# SignalAnalyse.net
KiCad netlist of a schematic drawn in Altium Designer
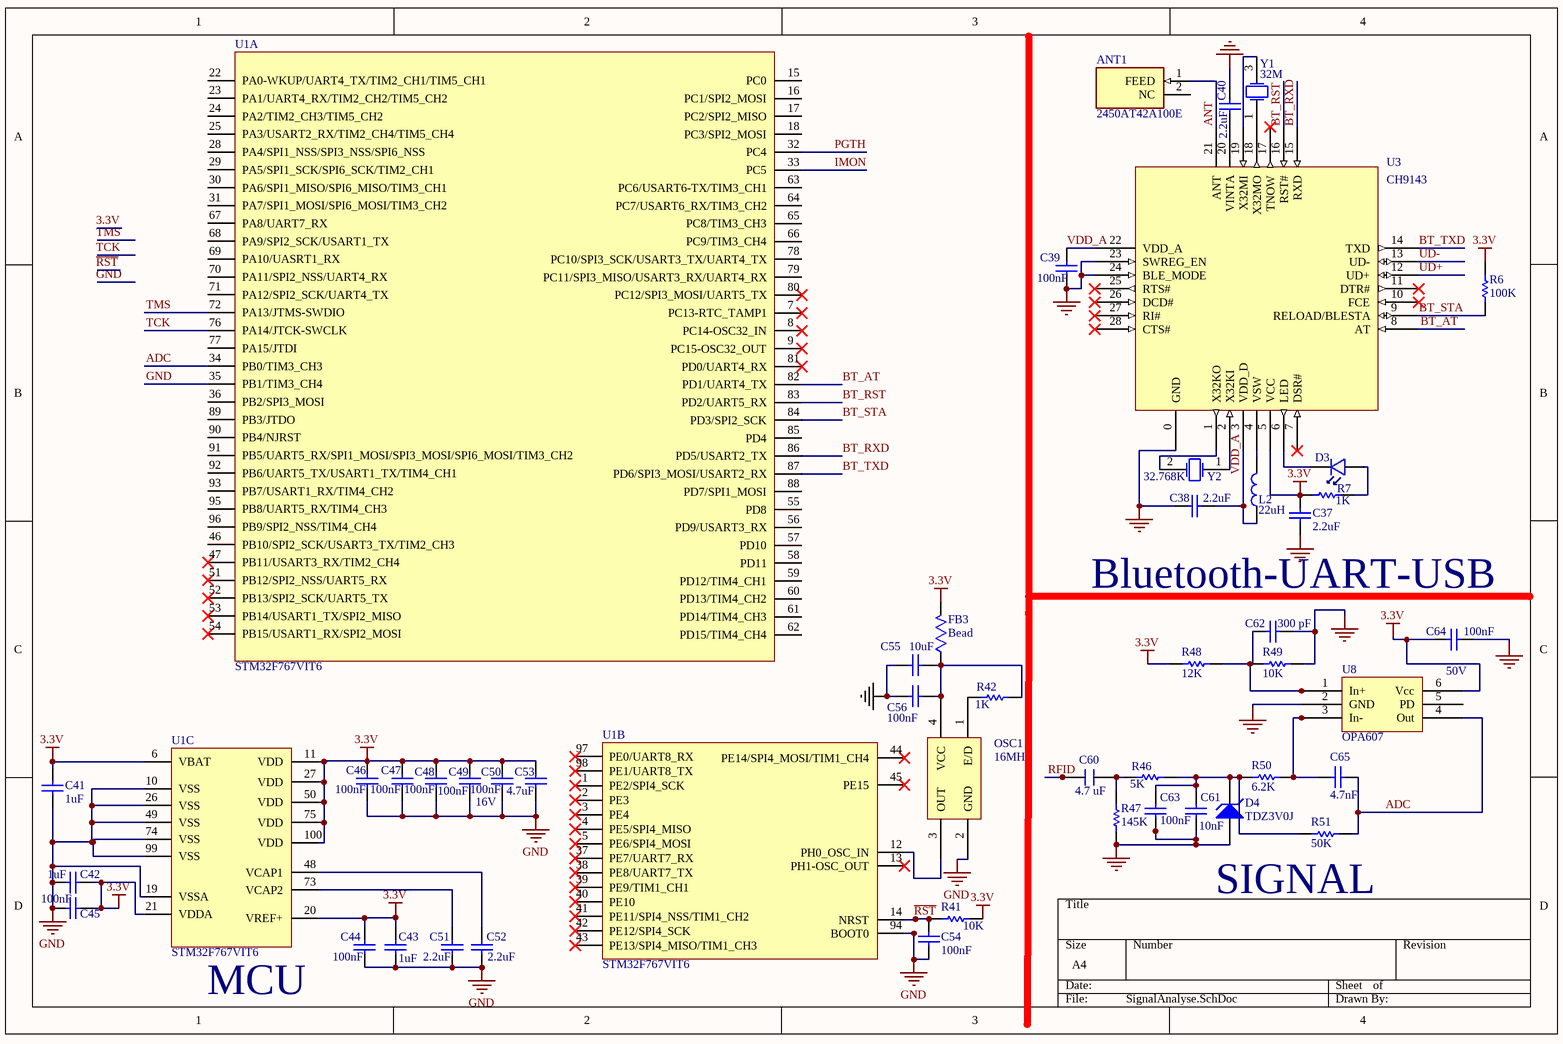
[diagram p0: SignalAnalyse.SchDoc]

(export (version "E")
  (design (tool "Eeschema 10.0.6"))
  (components
    (comp (ref "ANT1")
      (value "2450AT42A100E")
      (footprint "SamacSys:ANTC5020X110N")
      (description "Antenna")
      (fields (field (name "MOUSER PART NUMBER") "609-2450AT42A100E"))
      (libsource (lib "*") (part "2450AT42A100E"))
    )
    (comp (ref "C37")
      (value "2.2uF")
      (footprint "0603")
      (description "Capacitor (Semiconductor SIM Model)")
      (fields
        (field (name "VOLTAGE") "10V")
        (field (name "Comment") "GRM188R61A226ME15D")
        (field (name "PUBLISHER") "Altium Limited")
      )
      (libsource (lib "Miscellaneous Devices") (part "Cap Semi"))
    )
    (comp (ref "C38")
      (value "2.2uF")
      (footprint "0603")
      (description "Capacitor (Semiconductor SIM Model)")
      (fields
        (field (name "VOLTAGE") "10V")
        (field (name "Comment") "GRM188R61A226ME15D")
        (field (name "PUBLISHER") "Altium Limited")
      )
      (libsource (lib "Miscellaneous Devices") (part "Cap Semi"))
    )
    (comp (ref "C39")
      (value "100nF")
      (footprint "1608[0603]")
      (description "多层陶瓷电容器MLCC - SMD/SMT 0.1UF 16V 10% 0603")
      (fields
        (field (name "VOLTAGE") "16V")
        (field (name "PART NUMBER") "GCM188R71C104KA37J")
        (field (name "PUBLISHER") "Altium Limited")
      )
      (libsource (lib "Miscellaneous Devices") (part "Cap Semi"))
    )
    (comp (ref "C40")
      (value "2.2uF")
      (footprint "1608[0603]")
      (description "Capacitor (Semiconductor SIM Model)")
      (fields
        (field (name "VOLTAGE") "10V")
        (field (name "Comment") "GRM188R61A226ME15D")
        (field (name "PUBLISHER") "Altium Limited")
      )
      (libsource (lib "Miscellaneous Devices") (part "Cap Semi"))
    )
    (comp (ref "C41")
      (value "1uF")
      (footprint "1608[0603]")
      (description "Capacitor (Semiconductor SIM Model)")
      (fields
        (field (name "VOLTAGE") "50V")
        (field (name "Comment") "GRM188R61A226ME15D")
        (field (name "PUBLISHER") "Altium Limited")
      )
      (libsource (lib "Miscellaneous Devices") (part "Cap Semi"))
    )
    (comp (ref "C42")
      (value "1uF")
      (footprint "1608[0603]")
      (description "Capacitor (Semiconductor SIM Model)")
      (fields
        (field (name "VOLTAGE") "50V")
        (field (name "Comment") "GRM188R61A226ME15D")
        (field (name "PUBLISHER") "Altium Limited")
      )
      (libsource (lib "Miscellaneous Devices") (part "Cap Semi"))
    )
    (comp (ref "C43")
      (value "1uF")
      (footprint "1608[0603]")
      (description "Capacitor (Semiconductor SIM Model)")
      (fields
        (field (name "VOLTAGE") "50V")
        (field (name "Comment") "GRM188R61A226ME15D")
        (field (name "PUBLISHER") "Altium Limited")
      )
      (libsource (lib "Miscellaneous Devices") (part "Cap Semi"))
    )
    (comp (ref "C44")
      (value "100nF")
      (footprint "1608[0603]")
      (description "多层陶瓷电容器MLCC - SMD/SMT 0.1UF 16V 10% 0603")
      (fields
        (field (name "VOLTAGE") "16V")
        (field (name "PART NUMBER") "GCM188R71C104KA37J")
        (field (name "PUBLISHER") "Altium Limited")
      )
      (libsource (lib "Miscellaneous Devices") (part "Cap Semi"))
    )
    (comp (ref "C45")
      (value "100nF")
      (footprint "1608[0603]")
      (description "多层陶瓷电容器MLCC - SMD/SMT 0.1UF 16V 10% 0603")
      (fields
        (field (name "VOLTAGE") "16V")
        (field (name "PART NUMBER") "GCM188R71C104KA37J")
        (field (name "PUBLISHER") "Altium Limited")
      )
      (libsource (lib "Miscellaneous Devices") (part "Cap Semi"))
    )
    (comp (ref "C46")
      (value "100nF")
      (footprint "1608[0603]")
      (description "多层陶瓷电容器MLCC - SMD/SMT 0.1UF 16V 10% 0603")
      (fields
        (field (name "VOLTAGE") "16V")
        (field (name "PART NUMBER") "GCM188R71C104KA37J")
        (field (name "PUBLISHER") "Altium Limited")
      )
      (libsource (lib "Miscellaneous Devices") (part "Cap Semi"))
    )
    (comp (ref "C47")
      (value "100nF")
      (footprint "1608[0603]")
      (description "多层陶瓷电容器MLCC - SMD/SMT 0.1UF 16V 10% 0603")
      (fields
        (field (name "VOLTAGE") "16V")
        (field (name "PART NUMBER") "GCM188R71C104KA37J")
        (field (name "PUBLISHER") "Altium Limited")
      )
      (libsource (lib "Miscellaneous Devices") (part "Cap Semi"))
    )
    (comp (ref "C48")
      (value "100nF")
      (footprint "1608[0603]")
      (description "多层陶瓷电容器MLCC - SMD/SMT 0.1UF 16V 10% 0603")
      (fields
        (field (name "VOLTAGE") "16V")
        (field (name "PART NUMBER") "GCM188R71C104KA37J")
        (field (name "PUBLISHER") "Altium Limited")
      )
      (libsource (lib "Miscellaneous Devices") (part "Cap Semi"))
    )
    (comp (ref "C49")
      (value "100nF")
      (footprint "1608[0603]")
      (description "多层陶瓷电容器MLCC - SMD/SMT 0.1UF 16V 10% 0603")
      (fields
        (field (name "VOLTAGE") "16V")
        (field (name "PART NUMBER") "GCM188R71C104KA37J")
        (field (name "PUBLISHER") "Altium Limited")
      )
      (libsource (lib "Miscellaneous Devices") (part "Cap Semi"))
    )
    (comp (ref "C50")
      (value "100nF")
      (footprint "1608[0603]")
      (description "多层陶瓷电容器MLCC - SMD/SMT 0.1UF 16V 10% 0603")
      (fields
        (field (name "VOLTAGE") "16V")
        (field (name "PART NUMBER") "GCM188R71C104KA37J")
        (field (name "Comment") "Cap 100nF")
        (field (name "PUBLISHER") "Altium Limited")
      )
      (libsource (lib "Miscellaneous Devices") (part "Cap Semi"))
    )
    (comp (ref "C51")
      (value "2.2uF")
      (footprint "1608[0603]")
      (description "Capacitor (Semiconductor SIM Model)")
      (fields
        (field (name "VOLTAGE") "16V")
        (field (name "Comment") "GRM188R61A226ME15D")
        (field (name "PUBLISHER") "Altium Limited")
      )
      (libsource (lib "Miscellaneous Devices") (part "Cap Semi"))
    )
    (comp (ref "C52")
      (value "2.2uF")
      (footprint "1608[0603]")
      (description "Capacitor (Semiconductor SIM Model)")
      (fields
        (field (name "VOLTAGE") "16V")
        (field (name "Comment") "GRM188R61A226ME15D")
        (field (name "PUBLISHER") "Altium Limited")
      )
      (libsource (lib "Miscellaneous Devices") (part "Cap Semi"))
    )
    (comp (ref "C53")
      (value "4.7uF")
      (footprint "1608[0603]")
      (description "Capacitor (Semiconductor SIM Model)")
      (fields
        (field (name "VOLTAGE") "10V")
        (field (name "Comment") "GRM188R61A226ME15D")
        (field (name "PUBLISHER") "Altium Limited")
      )
      (libsource (lib "Miscellaneous Devices") (part "Cap Semi"))
    )
    (comp (ref "C54")
      (value "100nF")
      (footprint "1608[0603]")
      (description "多层陶瓷电容器MLCC - SMD/SMT 0.1UF 16V 10% 0603")
      (fields
        (field (name "VOLTAGE") "16V")
        (field (name "PART NUMBER") "GCM188R71C104KA37J")
        (field (name "PUBLISHER") "Altium Limited")
      )
      (libsource (lib "Miscellaneous Devices") (part "Cap Semi"))
    )
    (comp (ref "C55")
      (value "10uF")
      (footprint "1608[0603]")
      (description "多层陶瓷电容器MLCC - SMD/SMT 10UF 25V 10% 0603")
      (fields
        (field (name "VOLTAGE") "25V")
        (field (name "PART NUMBER") "GRM188R61E106KA73D")
        (field (name "PUBLISHER") "Altium Limited")
      )
      (libsource (lib "Miscellaneous Devices") (part "Cap Semi"))
    )
    (comp (ref "C56")
      (value "100nF")
      (footprint "1608[0603]")
      (description "多层陶瓷电容器MLCC - SMD/SMT 0.1UF 16V 10% 0603")
      (fields
        (field (name "VOLTAGE") "16V")
        (field (name "PART NUMBER") "GCM188R71C104KA37J")
        (field (name "PUBLISHER") "Altium Limited")
      )
      (libsource (lib "Miscellaneous Devices") (part "Cap Semi"))
    )
    (comp (ref "C60")
      (value "4.7 uF")
      (footprint "0603")
      (description "多层陶瓷电容器MLCC - SMD/SMT 0603 4.7uF 25V X5R 20%")
      (fields (field (name "VOLTAGE") "25V") (field (name "PART NUMBER") "GRM188R61E475ME11J"))
      (libsource (lib "Integrated_Library") (part "C-Ceramic"))
    )
    (comp (ref "C61")
      (value "10nF")
      (footprint "1608[0603]")
      (description "多层陶瓷电容器MLCC - SMD/SMT 0.01UF 25V 5% 0603 C0G")
      (fields
        (field (name "VOLTAGE") "25V")
        (field (name "PART NUMBER") "GRM1885C1E103JA01D")
        (field (name "PUBLISHER") "Altium Limited")
      )
      (libsource (lib "Miscellaneous Devices") (part "Cap Semi"))
    )
    (comp (ref "C62")
      (value "300 pF")
      (footprint "1608[0603]")
      (description "多层陶瓷电容器MLCC - SMD/SMT 0603 300pF 50volts C0G 2%")
      (fields
        (field (name "VOLTAGE") "50V")
        (field (name "PART NUMBER") "GRM1885C1H301GA01D")
        (field (name "PUBLISHER") "Altium Limited")
      )
      (libsource (lib "Miscellaneous Devices") (part "Cap Semi"))
    )
    (comp (ref "C63")
      (value "100nF")
      (footprint "1608[0603]")
      (description "多层陶瓷电容器MLCC - SMD/SMT 100nF+/-10% 50V X7R 1608")
      (fields
        (field (name "VOLTAGE") "50V")
        (field (name "PART NUMBER") "CL10B104KB8NNNC")
        (field (name "PUBLISHER") "Altium Limited")
      )
      (libsource (lib "Miscellaneous Devices") (part "Cap Semi"))
    )
    (comp (ref "C64")
      (value "100nF")
      (footprint "1608[0603]")
      (description "多层陶瓷电容器MLCC - SMD/SMT 100nF+/-10% 50V X7R 1608")
      (fields
        (field (name "VOLTAGE") "50V")
        (field (name "PART NUMBER") "GCM188R71C104KA37J")
        (field (name "Comment") "Cap 100nF")
        (field (name "PUBLISHER") "Altium Limited")
      )
      (libsource (lib "Miscellaneous Devices") (part "Cap Semi"))
    )
    (comp (ref "C65")
      (value "4.7nF")
      (footprint "1608[0603]")
      (description "多层陶瓷电容器MLCC - SMD/SMT 16V 4700pF X7R 0603 10%")
      (fields
        (field (name "VOLTAGE") "16V")
        (field (name "PART NUMBER") "CC0603KRX7R7BB472")
        (field (name "PUBLISHER") "Altium Limited")
      )
      (libsource (lib "Miscellaneous Devices") (part "Cap Semi"))
    )
    (comp (ref "D3")
      (value "LED-Green")
      (footprint "D0805")
      (libsource (lib "Integrated_Library") (part "LED"))
    )
    (comp (ref "D4")
      (value "TDZ3V0J")
      (footprint "SOD-323")
      (description "Zener Diode 3V")
      (fields (field (name "PUBLISHER") "Altium Limited"))
      (libsource (lib "Miscellaneous Devices") (part "D Zener"))
    )
    (comp (ref "FB3")
      (value "Bead")
      (footprint "SamacSys:BEADC2012X110N")
      (description "Wurth Ferrite Bead")
      (fields (field (name "MANUFACTURER_PART_NUMBER") "782853200"))
      (libsource (lib "SamacSys") (part "782853200"))
    )
    (comp (ref "L2")
      (value "22uH")
      (footprint "L0805")
      (fields (field (name "PART NUMBER") "MGFL2012F220") (field (name "MANUFACTURER") "microgate"))
      (libsource (lib "Integrated_Library") (part "FB"))
    )
    (comp (ref "OSC1")
      (value "16MHz")
      (footprint "OSC_3.2X2.5")
      (description "OSC with disable function")
      (libsource (lib "Integrated_Library") (part "OSC2"))
    )
    (comp (ref "R6")
      (value "100K")
      (footprint "J1-0603")
      (description "Resistor")
      (fields
        (field (name "PART NUMBER") "RC0603FR-07100KL")
        (field (name "MANUFACTURER") "YAGEO")
        (field (name "PUBLISHER") "Altium Limited")
      )
      (libsource (lib "Miscellaneous Devices") (part "Res1"))
    )
    (comp (ref "R7")
      (value "1K")
      (footprint "J1-0603")
      (description "Resistor")
      (fields
        (field (name "PART NUMBER") "RC0603FR-071KL")
        (field (name "MANUFACTURER") "YAGEO")
        (field (name "PUBLISHER") "Altium Limited")
      )
      (libsource (lib "Miscellaneous Devices") (part "Res1"))
    )
    (comp (ref "R41")
      (value "10K")
      (footprint "J1-0603")
      (description "Resistor")
      (fields
        (field (name "PART NUMBER") "RC0603FR-0710KL")
        (field (name "MANUFACTURER") "YAGEO")
        (field (name "PUBLISHER") "Altium Limited")
      )
      (libsource (lib "Miscellaneous Devices") (part "Res1"))
    )
    (comp (ref "R42")
      (value "1K")
      (footprint "J1-0603")
      (description "Resistor")
      (fields
        (field (name "PART NUMBER") "RC0603FR-071KL")
        (field (name "MANUFACTURER") "YAGEO")
        (field (name "PUBLISHER") "Altium Limited")
      )
      (libsource (lib "Miscellaneous Devices") (part "Res1"))
    )
    (comp (ref "R46")
      (value "5K")
      (footprint "J1-0603")
      (description "Resistor")
      (fields
        (field (name "PART NUMBER") "RC0603FR-071KL")
        (field (name "MANUFACTURER") "YAGEO")
        (field (name "PUBLISHER") "Altium Limited")
      )
      (libsource (lib "Miscellaneous Devices") (part "Res1"))
    )
    (comp (ref "R47")
      (value "145K")
      (footprint "J1-0603")
      (description "Resistor")
      (fields
        (field (name "PART NUMBER") "RC0603FR-0710KL")
        (field (name "MANUFACTURER") "YAGEO")
        (field (name "PUBLISHER") "Altium Limited")
      )
      (libsource (lib "Miscellaneous Devices") (part "Res1"))
    )
    (comp (ref "R48")
      (value "12K")
      (footprint "J1-0603")
      (description "Resistor")
      (fields
        (field (name "PART NUMBER") "RC0603FR-0710KL")
        (field (name "MANUFACTURER") "YAGEO")
        (field (name "PUBLISHER") "Altium Limited")
      )
      (libsource (lib "Miscellaneous Devices") (part "Res1"))
    )
    (comp (ref "R49")
      (value "10K")
      (footprint "J1-0603")
      (description "Resistor")
      (fields
        (field (name "PART NUMBER") "RC0603FR-0710KL")
        (field (name "MANUFACTURER") "YAGEO")
        (field (name "PUBLISHER") "Altium Limited")
      )
      (libsource (lib "Miscellaneous Devices") (part "Res1"))
    )
    (comp (ref "R50")
      (value "6.2K")
      (footprint "J1-0603")
      (description "Resistor")
      (fields
        (field (name "PART NUMBER") "RC0603FR-0710KL")
        (field (name "MANUFACTURER") "YAGEO")
        (field (name "PUBLISHER") "Altium Limited")
      )
      (libsource (lib "Miscellaneous Devices") (part "Res1"))
    )
    (comp (ref "R51")
      (value "50K")
      (footprint "J1-0603")
      (description "Resistor")
      (fields
        (field (name "PART NUMBER") "RC0603FR-0710KL")
        (field (name "MANUFACTURER") "YAGEO")
        (field (name "PUBLISHER") "Altium Limited")
      )
      (libsource (lib "Miscellaneous Devices") (part "Res1"))
    )
    (comp (ref "U1")
      (value "STM32F767VIT6")
      (footprint "STM32F767VIT6")
      (libsource (lib "") (part "STM32F767VIT6_1"))
    )
    (comp (ref "U3")
      (value "CH9143")
      (footprint "QFN28_4X4")
      (description "Bluetooth-LowEnergy & UART & USB Mutual Transport")
      (libsource (lib "CHXXX") (part "CH9143"))
    )
    (comp (ref "U8")
      (value "OPA607")
      (footprint "OPA607IDCKR")
      (libsource (lib "OPA607IDCKR") (part "TSV620AILT"))
    )
    (comp (ref "Y1")
      (value "32M")
      (footprint "SamacSys:SMD2016-4N")
      (description "Quartz Crystal Oscillator")
      (fields (field (name "MANUFACTURER_PART_NUMBER") "X201632MMB4SI"))
      (libsource (lib "SamacSys") (part "X201632MMB4SI"))
    )
    (comp (ref "Y2")
      (value "32.768K")
      (footprint "SamacSys:Q13FC1350000400")
      (description "Crystal Oscillator")
      (fields (field (name "MANUFACTURER_PART_NUMBER") "Q13FC1350000400"))
      (libsource (lib "SamacSys") (part "Q13FC1350000400"))
    )
  )
  (nets
    (net (code "1") (name "/ADC") (class "Default")
      (node (ref "C65") (pin "1") (pinfunction "1_1") (pintype "passive"))
      (node (ref "R51") (pin "1") (pinfunction "1_1") (pintype "passive"))
      (node (ref "U1") (pin "34") (pinfunction "PB0/TIM3_CH3_34") (pintype "passive"))
      (node (ref "U8") (pin "4") (pinfunction "Out_4") (pintype "passive"))
    )
    (net (code "2") (name "/ANT") (class "Default")
      (node (ref "ANT1") (pin "1") (pinfunction "FEED_1") (pintype "input"))
      (node (ref "U3") (pin "21") (pinfunction "ANT_21") (pintype "passive"))
    )
    (net (code "3") (name "/BT_AT") (class "Default")
      (node (ref "U1") (pin "82") (pinfunction "PD1/UART4_TX_82") (pintype "passive"))
      (node (ref "U3") (pin "8") (pinfunction "AT_8") (pintype "input"))
    )
    (net (code "4") (name "/BT_RST") (class "Default")
      (node (ref "U1") (pin "83") (pinfunction "PD2/UART5_RX_83") (pintype "passive"))
      (node (ref "U3") (pin "16") (pinfunction "RST#_16") (pintype "input"))
    )
    (net (code "5") (name "/BT_RXD") (class "Default")
      (node (ref "U1") (pin "86") (pinfunction "PD5/USART2_TX_86") (pintype "passive"))
      (node (ref "U3") (pin "15") (pinfunction "RXD_15") (pintype "input"))
    )
    (net (code "6") (name "/BT_STA") (class "Default")
      (node (ref "R6") (pin "2") (pinfunction "2_2") (pintype "passive"))
      (node (ref "U1") (pin "84") (pinfunction "PD3/SPI2_SCK_84") (pintype "passive"))
      (node (ref "U3") (pin "9") (pinfunction "RELOAD/BLESTA_9") (pintype "bidirectional"))
    )
    (net (code "7") (name "/BT_TXD") (class "Default")
      (node (ref "U1") (pin "87") (pinfunction "PD6/SPI3_MOSI/USART2_RX_87") (pintype "passive"))
      (node (ref "U3") (pin "14") (pinfunction "TXD_14") (pintype "output"))
    )
    (net (code "8") (name "/IMON") (class "Default")
      (node (ref "U1") (pin "33") (pinfunction "PC5_33") (pintype "passive"))
    )
    (net (code "9") (name "/PGTH") (class "Default")
      (node (ref "U1") (pin "32") (pinfunction "PC4_32") (pintype "passive"))
    )
    (net (code "10") (name "/RFID") (class "Default")
      (node (ref "C60") (pin "1") (pinfunction "1_1") (pintype "passive"))
    )
    (net (code "11") (name "/TCK") (class "Default")
      (node (ref "U1") (pin "76") (pinfunction "PA14/JTCK-SWCLK_76") (pintype "passive"))
    )
    (net (code "12") (name "/TMS") (class "Default")
      (node (ref "U1") (pin "72") (pinfunction "PA13/JTMS-SWDIO_72") (pintype "passive"))
    )
    (net (code "13") (name "/UD+") (class "Default")
      (node (ref "U3") (pin "12") (pinfunction "UD+_12") (pintype "bidirectional"))
    )
    (net (code "14") (name "/UD-") (class "Default")
      (node (ref "U3") (pin "13") (pinfunction "UD-_13") (pintype "bidirectional"))
    )
    (net (code "15") (name "/VDD_A") (class "Default")
      (node (ref "C38") (pin "2") (pinfunction "2_2") (pintype "passive"))
      (node (ref "C39") (pin "1") (pinfunction "1_1") (pintype "passive"))
      (node (ref "L2") (pin "1") (pinfunction "1_1") (pintype "passive"))
      (node (ref "U3") (pin "22") (pinfunction "VDD_A_22") (pintype "power_in"))
      (node (ref "U3") (pin "3") (pinfunction "VDD_D_3") (pintype "power_in"))
    )
    (net (code "16") (name "/~{RST}") (class "Default")
      (node (ref "C54") (pin "1") (pinfunction "1_1") (pintype "passive"))
      (node (ref "R41") (pin "1") (pinfunction "1_1") (pintype "passive"))
      (node (ref "U1") (pin "14") (pinfunction "NRST_14") (pintype "passive"))
    )
    (net (code "17") (name "3.3V") (class "Default")
      (node (ref "C37") (pin "2") (pinfunction "2_2") (pintype "passive"))
      (node (ref "C41") (pin "1") (pinfunction "1_1") (pintype "passive"))
      (node (ref "C42") (pin "1") (pinfunction "1_1") (pintype "passive"))
      (node (ref "C43") (pin "2") (pinfunction "2_2") (pintype "passive"))
      (node (ref "C44") (pin "2") (pinfunction "2_2") (pintype "passive"))
      (node (ref "C45") (pin "1") (pinfunction "1_1") (pintype "passive"))
      (node (ref "C46") (pin "2") (pinfunction "2_2") (pintype "passive"))
      (node (ref "C47") (pin "2") (pinfunction "2_2") (pintype "passive"))
      (node (ref "C48") (pin "2") (pinfunction "2_2") (pintype "passive"))
      (node (ref "C49") (pin "2") (pinfunction "2_2") (pintype "passive"))
      (node (ref "C50") (pin "2") (pinfunction "2_2") (pintype "passive"))
      (node (ref "C53") (pin "2") (pinfunction "2_2") (pintype "passive"))
      (node (ref "C64") (pin "2") (pinfunction "2_2") (pintype "passive"))
      (node (ref "FB3") (pin "2") (pinfunction "2_2") (pintype "passive"))
      (node (ref "R41") (pin "2") (pinfunction "2_2") (pintype "passive"))
      (node (ref "R48") (pin "2") (pinfunction "2_2") (pintype "passive"))
      (node (ref "R6") (pin "1") (pinfunction "1_1") (pintype "passive"))
      (node (ref "R7") (pin "1") (pinfunction "1_1") (pintype "passive"))
      (node (ref "U1") (pin "100") (pinfunction "VDD_100") (pintype "passive"))
      (node (ref "U1") (pin "11") (pinfunction "VDD_11") (pintype "passive"))
      (node (ref "U1") (pin "20") (pinfunction "VREF+_20") (pintype "passive"))
      (node (ref "U1") (pin "21") (pinfunction "VDDA_21") (pintype "passive"))
      (node (ref "U1") (pin "27") (pinfunction "VDD_27") (pintype "passive"))
      (node (ref "U1") (pin "50") (pinfunction "VDD_50") (pintype "passive"))
      (node (ref "U1") (pin "6") (pinfunction "VBAT_6") (pintype "passive"))
      (node (ref "U1") (pin "75") (pinfunction "VDD_75") (pintype "passive"))
      (node (ref "U3") (pin "5") (pinfunction "VCC_5") (pintype "power_in"))
      (node (ref "U8") (pin "6") (pinfunction "Vcc_6") (pintype "passive"))
    )
    (net (code "18") (name "GND") (class "Default")
      (node (ref "C37") (pin "1") (pinfunction "1_1") (pintype "passive"))
      (node (ref "C38") (pin "1") (pinfunction "1_1") (pintype "passive"))
      (node (ref "C39") (pin "2") (pinfunction "2_2") (pintype "passive"))
      (node (ref "C40") (pin "1") (pinfunction "1_1") (pintype "passive"))
      (node (ref "C41") (pin "2") (pinfunction "2_2") (pintype "passive"))
      (node (ref "C42") (pin "2") (pinfunction "2_2") (pintype "passive"))
      (node (ref "C43") (pin "1") (pinfunction "1_1") (pintype "passive"))
      (node (ref "C44") (pin "1") (pinfunction "1_1") (pintype "passive"))
      (node (ref "C45") (pin "2") (pinfunction "2_2") (pintype "passive"))
      (node (ref "C46") (pin "1") (pinfunction "1_1") (pintype "passive"))
      (node (ref "C47") (pin "1") (pinfunction "1_1") (pintype "passive"))
      (node (ref "C48") (pin "1") (pinfunction "1_1") (pintype "passive"))
      (node (ref "C49") (pin "1") (pinfunction "1_1") (pintype "passive"))
      (node (ref "C50") (pin "1") (pinfunction "1_1") (pintype "passive"))
      (node (ref "C51") (pin "1") (pinfunction "1_1") (pintype "passive"))
      (node (ref "C52") (pin "1") (pinfunction "1_1") (pintype "passive"))
      (node (ref "C53") (pin "1") (pinfunction "1_1") (pintype "passive"))
      (node (ref "C54") (pin "2") (pinfunction "2_2") (pintype "passive"))
      (node (ref "C55") (pin "2") (pinfunction "2_2") (pintype "passive"))
      (node (ref "C56") (pin "2") (pinfunction "2_2") (pintype "passive"))
      (node (ref "C61") (pin "1") (pinfunction "1_1") (pintype "passive"))
      (node (ref "C62") (pin "1") (pinfunction "1_1") (pintype "passive"))
      (node (ref "C63") (pin "1") (pinfunction "1_1") (pintype "passive"))
      (node (ref "C64") (pin "1") (pinfunction "1_1") (pintype "passive"))
      (node (ref "D4") (pin "1") (pinfunction "A_1") (pintype "passive"))
      (node (ref "OSC1") (pin "2") (pinfunction "GND_2") (pintype "passive"))
      (node (ref "R47") (pin "2") (pinfunction "2_2") (pintype "passive"))
      (node (ref "R49") (pin "2") (pinfunction "2_2") (pintype "passive"))
      (node (ref "U1") (pin "10") (pinfunction "VSS_10") (pintype "passive"))
      (node (ref "U1") (pin "19") (pinfunction "VSSA_19") (pintype "passive"))
      (node (ref "U1") (pin "26") (pinfunction "VSS_26") (pintype "passive"))
      (node (ref "U1") (pin "35") (pinfunction "PB1/TIM3_CH4_35") (pintype "passive"))
      (node (ref "U1") (pin "49") (pinfunction "VSS_49") (pintype "passive"))
      (node (ref "U1") (pin "74") (pinfunction "VSS_74") (pintype "passive"))
      (node (ref "U1") (pin "94") (pinfunction "BOOT0_94") (pintype "passive"))
      (node (ref "U1") (pin "99") (pinfunction "VSS_99") (pintype "passive"))
      (node (ref "U3") (pin "0") (pinfunction "GND_0") (pintype "power_in"))
      (node (ref "U3") (pin "23") (pinfunction "SWREG_EN_23") (pintype "input"))
      (node (ref "U3") (pin "24") (pinfunction "BLE_MODE_24") (pintype "input"))
      (node (ref "U8") (pin "2") (pinfunction "GND_2") (pintype "passive"))
    )
    (net (code "19") (name "Net-(C60-Pad2)") (class "Default")
      (node (ref "C60") (pin "2") (pinfunction "2_2") (pintype "passive"))
      (node (ref "R46") (pin "1") (pinfunction "1_1") (pintype "passive"))
      (node (ref "R47") (pin "1") (pinfunction "1_1") (pintype "passive"))
    )
    (net (code "20") (name "Net-(D3-Pad1)") (class "Default")
      (node (ref "D3") (pin "1") (pinfunction "1_1") (pintype "passive"))
      (node (ref "R7") (pin "2") (pinfunction "2_2") (pintype "passive"))
    )
    (net (code "21") (name "Net-(D4-K)") (class "Default")
      (node (ref "C61") (pin "2") (pinfunction "2_2") (pintype "passive"))
      (node (ref "C63") (pin "2") (pinfunction "2_2") (pintype "passive"))
      (node (ref "D4") (pin "2") (pinfunction "K_2") (pintype "passive"))
      (node (ref "R46") (pin "2") (pinfunction "2_2") (pintype "passive"))
      (node (ref "R50") (pin "2") (pinfunction "2_2") (pintype "passive"))
      (node (ref "R51") (pin "2") (pinfunction "2_2") (pintype "passive"))
    )
    (net (code "22") (name "Net-(OSC1-E{slash}D)") (class "Default")
      (node (ref "OSC1") (pin "1") (pinfunction "E/D_1") (pintype "passive"))
      (node (ref "R42") (pin "1") (pinfunction "1_1") (pintype "passive"))
    )
    (net (code "23") (name "Net-(OSC1-OUT)") (class "Default")
      (node (ref "OSC1") (pin "3") (pinfunction "OUT_3") (pintype "passive"))
      (node (ref "U1") (pin "12") (pinfunction "PH0_OSC_IN_12") (pintype "passive"))
    )
    (net (code "24") (name "Net-(OSC1-VCC)") (class "Default")
      (node (ref "C55") (pin "1") (pinfunction "1_1") (pintype "passive"))
      (node (ref "C56") (pin "1") (pinfunction "1_1") (pintype "passive"))
      (node (ref "FB3") (pin "1") (pinfunction "1_1") (pintype "passive"))
      (node (ref "OSC1") (pin "4") (pinfunction "VCC_4") (pintype "passive"))
      (node (ref "R42") (pin "2") (pinfunction "2_2") (pintype "passive"))
    )
    (net (code "25") (name "Net-(U1C-VCAP1)") (class "Default")
      (node (ref "C52") (pin "2") (pinfunction "2_2") (pintype "passive"))
      (node (ref "U1") (pin "48") (pinfunction "VCAP1_48") (pintype "passive"))
    )
    (net (code "26") (name "Net-(U1C-VCAP2)") (class "Default")
      (node (ref "C51") (pin "2") (pinfunction "2_2") (pintype "passive"))
      (node (ref "U1") (pin "73") (pinfunction "VCAP2_73") (pintype "passive"))
    )
    (net (code "27") (name "Net-(U3-LED)") (class "Default")
      (node (ref "D3") (pin "2") (pinfunction "2_2") (pintype "passive"))
      (node (ref "U3") (pin "6") (pinfunction "LED_6") (pintype "output"))
    )
    (net (code "28") (name "Net-(U3-VINTA)") (class "Default")
      (node (ref "C40") (pin "2") (pinfunction "2_2") (pintype "passive"))
      (node (ref "U3") (pin "20") (pinfunction "VINTA_20") (pintype "power_in"))
    )
    (net (code "29") (name "Net-(U3-VSW)") (class "Default")
      (node (ref "L2") (pin "2") (pinfunction "2_2") (pintype "passive"))
      (node (ref "U3") (pin "4") (pinfunction "VSW_4") (pintype "power_in"))
    )
    (net (code "30") (name "Net-(U3-X32KI)") (class "Default")
      (node (ref "U3") (pin "2") (pinfunction "X32KI_2") (pintype "input"))
      (node (ref "Y2") (pin "1") (pinfunction "CRYSTAL_1_1") (pintype "passive"))
    )
    (net (code "31") (name "Net-(U3-X32KO)") (class "Default")
      (node (ref "U3") (pin "1") (pinfunction "X32KO_1") (pintype "output"))
      (node (ref "Y2") (pin "2") (pinfunction "CRYSTAL_2_2") (pintype "passive"))
    )
    (net (code "32") (name "Net-(U3-X32MI)") (class "Default")
      (node (ref "U3") (pin "19") (pinfunction "X32MI_19") (pintype "input"))
      (node (ref "Y1") (pin "3") (pinfunction "OSC2_3") (pintype "passive"))
    )
    (net (code "33") (name "Net-(U3-X32MO)") (class "Default")
      (node (ref "U3") (pin "18") (pinfunction "X32MO_18") (pintype "output"))
      (node (ref "Y1") (pin "1") (pinfunction "OSC1_1") (pintype "passive"))
    )
    (net (code "34") (name "Net-(U8-In+)") (class "Default")
      (node (ref "C62") (pin "2") (pinfunction "2_2") (pintype "passive"))
      (node (ref "R48") (pin "1") (pinfunction "1_1") (pintype "passive"))
      (node (ref "R49") (pin "1") (pinfunction "1_1") (pintype "passive"))
      (node (ref "U8") (pin "1") (pinfunction "In+_1") (pintype "passive"))
    )
    (net (code "35") (name "Net-(U8-In-)") (class "Default")
      (node (ref "C65") (pin "2") (pinfunction "2_2") (pintype "passive"))
      (node (ref "R50") (pin "1") (pinfunction "1_1") (pintype "passive"))
      (node (ref "U8") (pin "3") (pinfunction "In-_3") (pintype "passive"))
    )
    (net (code "36") (name "unconnected-(ANT1-NC-Pad2)") (class "Default")
      (node (ref "ANT1") (pin "2") (pinfunction "NC_2") (pintype "passive"))
    )
    (net (code "37") (name "unconnected-(U1A-PA0-WKUP{slash}UART4_TX{slash}TIM2_CH1{slash}TIM5_CH1-Pad22)") (class "Default")
      (node (ref "U1") (pin "22") (pinfunction "PA0-WKUP/UART4_TX/TIM2_CH1/TIM5_CH1_22") (pintype "passive"))
    )
    (net (code "38") (name "unconnected-(U1A-PA1{slash}UART4_RX{slash}TIM2_CH2{slash}TIM5_CH2-Pad23)") (class "Default")
      (node (ref "U1") (pin "23") (pinfunction "PA1/UART4_RX/TIM2_CH2/TIM5_CH2_23") (pintype "passive"))
    )
    (net (code "39") (name "unconnected-(U1A-PA2{slash}TIM2_CH3{slash}TIM5_CH2-Pad24)") (class "Default")
      (node (ref "U1") (pin "24") (pinfunction "PA2/TIM2_CH3/TIM5_CH2_24") (pintype "passive"))
    )
    (net (code "40") (name "unconnected-(U1A-PA3{slash}USART2_RX{slash}TIM2_CH4{slash}TIM5_CH4-Pad25)") (class "Default")
      (node (ref "U1") (pin "25") (pinfunction "PA3/USART2_RX/TIM2_CH4/TIM5_CH4_25") (pintype "passive"))
    )
    (net (code "41") (name "unconnected-(U1A-PA4{slash}SPI1_NSS{slash}SPI3_NSS{slash}SPI6_NSS-Pad28)") (class "Default")
      (node (ref "U1") (pin "28") (pinfunction "PA4/SPI1_NSS/SPI3_NSS/SPI6_NSS_28") (pintype "passive"))
    )
    (net (code "42") (name "unconnected-(U1A-PA5{slash}SPI1_SCK{slash}SPI6_SCK{slash}TIM2_CH1-Pad29)") (class "Default")
      (node (ref "U1") (pin "29") (pinfunction "PA5/SPI1_SCK/SPI6_SCK/TIM2_CH1_29") (pintype "passive"))
    )
    (net (code "43") (name "unconnected-(U1A-PA6{slash}SPI1_MISO{slash}SPI6_MISO{slash}TIM3_CH1-Pad30)") (class "Default")
      (node (ref "U1") (pin "30") (pinfunction "PA6/SPI1_MISO/SPI6_MISO/TIM3_CH1_30") (pintype "passive"))
    )
    (net (code "44") (name "unconnected-(U1A-PA7{slash}SPI1_MOSI{slash}SPI6_MOSI{slash}TIM3_CH2-Pad31)") (class "Default")
      (node (ref "U1") (pin "31") (pinfunction "PA7/SPI1_MOSI/SPI6_MOSI/TIM3_CH2_31") (pintype "passive"))
    )
    (net (code "45") (name "unconnected-(U1A-PA8{slash}UART7_RX-Pad67)") (class "Default")
      (node (ref "U1") (pin "67") (pinfunction "PA8/UART7_RX_67") (pintype "passive"))
    )
    (net (code "46") (name "unconnected-(U1A-PA9{slash}SPI2_SCK{slash}USART1_TX-Pad68)") (class "Default")
      (node (ref "U1") (pin "68") (pinfunction "PA9/SPI2_SCK/USART1_TX_68") (pintype "passive"))
    )
    (net (code "47") (name "unconnected-(U1A-PA10{slash}UASRT1_RX-Pad69)") (class "Default")
      (node (ref "U1") (pin "69") (pinfunction "PA10/UASRT1_RX_69") (pintype "passive"))
    )
    (net (code "48") (name "unconnected-(U1A-PA11{slash}SPI2_NSS{slash}UART4_RX-Pad70)") (class "Default")
      (node (ref "U1") (pin "70") (pinfunction "PA11/SPI2_NSS/UART4_RX_70") (pintype "passive"))
    )
    (net (code "49") (name "unconnected-(U1A-PA12{slash}SPI2_SCK{slash}UART4_TX-Pad71)") (class "Default")
      (node (ref "U1") (pin "71") (pinfunction "PA12/SPI2_SCK/UART4_TX_71") (pintype "passive"))
    )
    (net (code "50") (name "unconnected-(U1A-PA15{slash}JTDI-Pad77)") (class "Default")
      (node (ref "U1") (pin "77") (pinfunction "PA15/JTDI_77") (pintype "passive"))
    )
    (net (code "51") (name "unconnected-(U1A-PB2{slash}SPI3_MOSI-Pad36)") (class "Default")
      (node (ref "U1") (pin "36") (pinfunction "PB2/SPI3_MOSI_36") (pintype "passive"))
    )
    (net (code "52") (name "unconnected-(U1A-PB3{slash}JTDO-Pad89)") (class "Default")
      (node (ref "U1") (pin "89") (pinfunction "PB3/JTDO_89") (pintype "passive"))
    )
    (net (code "53") (name "unconnected-(U1A-PB4{slash}NJRST-Pad90)") (class "Default")
      (node (ref "U1") (pin "90") (pinfunction "PB4/NJRST_90") (pintype "passive"))
    )
    (net (code "54") (name "unconnected-(U1A-PB5{slash}UART5_RX{slash}SPI1_MOSI{slash}SPI3_MOSI{slash}SPI6_MOSI{slash}TIM3_CH2-Pad91)") (class "Default")
      (node (ref "U1") (pin "91") (pinfunction "PB5/UART5_RX/SPI1_MOSI/SPI3_MOSI/SPI6_MOSI/TIM3_CH2_91") (pintype "passive"))
    )
    (net (code "55") (name "unconnected-(U1A-PB6{slash}UART5_TX{slash}USART1_TX{slash}TIM4_CH1-Pad92)") (class "Default")
      (node (ref "U1") (pin "92") (pinfunction "PB6/UART5_TX/USART1_TX/TIM4_CH1_92") (pintype "passive"))
    )
    (net (code "56") (name "unconnected-(U1A-PB7{slash}USART1_RX{slash}TIM4_CH2-Pad93)") (class "Default")
      (node (ref "U1") (pin "93") (pinfunction "PB7/USART1_RX/TIM4_CH2_93") (pintype "passive"))
    )
    (net (code "57") (name "unconnected-(U1A-PB8{slash}UART5_RX{slash}TIM4_CH3-Pad95)") (class "Default")
      (node (ref "U1") (pin "95") (pinfunction "PB8/UART5_RX/TIM4_CH3_95") (pintype "passive"))
    )
    (net (code "58") (name "unconnected-(U1A-PB9{slash}SPI2_NSS{slash}TIM4_CH4-Pad96)") (class "Default")
      (node (ref "U1") (pin "96") (pinfunction "PB9/SPI2_NSS/TIM4_CH4_96") (pintype "passive"))
    )
    (net (code "59") (name "unconnected-(U1A-PB10{slash}SPI2_SCK{slash}USART3_TX{slash}TIM2_CH3-Pad46)") (class "Default")
      (node (ref "U1") (pin "46") (pinfunction "PB10/SPI2_SCK/USART3_TX/TIM2_CH3_46") (pintype "passive"))
    )
    (net (code "60") (name "unconnected-(U1A-PB11{slash}USART3_RX{slash}TIM2_CH4-Pad47)") (class "Default")
      (node (ref "U1") (pin "47") (pinfunction "PB11/USART3_RX/TIM2_CH4_47") (pintype "passive+no_connect"))
    )
    (net (code "61") (name "unconnected-(U1A-PB12{slash}SPI2_NSS{slash}UART5_RX-Pad51)") (class "Default")
      (node (ref "U1") (pin "51") (pinfunction "PB12/SPI2_NSS/UART5_RX_51") (pintype "passive+no_connect"))
    )
    (net (code "62") (name "unconnected-(U1A-PB13{slash}SPI2_SCK{slash}UART5_TX-Pad52)") (class "Default")
      (node (ref "U1") (pin "52") (pinfunction "PB13/SPI2_SCK/UART5_TX_52") (pintype "passive+no_connect"))
    )
    (net (code "63") (name "unconnected-(U1A-PB14{slash}USART1_TX{slash}SPI2_MISO-Pad53)") (class "Default")
      (node (ref "U1") (pin "53") (pinfunction "PB14/USART1_TX/SPI2_MISO_53") (pintype "passive+no_connect"))
    )
    (net (code "64") (name "unconnected-(U1A-PB15{slash}USART1_RX{slash}SPI2_MOSI-Pad54)") (class "Default")
      (node (ref "U1") (pin "54") (pinfunction "PB15/USART1_RX/SPI2_MOSI_54") (pintype "passive+no_connect"))
    )
    (net (code "65") (name "unconnected-(U1A-PC0-Pad15)") (class "Default")
      (node (ref "U1") (pin "15") (pinfunction "PC0_15") (pintype "passive"))
    )
    (net (code "66") (name "unconnected-(U1A-PC1{slash}SPI2_MOSI-Pad16)") (class "Default")
      (node (ref "U1") (pin "16") (pinfunction "PC1/SPI2_MOSI_16") (pintype "passive"))
    )
    (net (code "67") (name "unconnected-(U1A-PC2{slash}SPI2_MISO-Pad17)") (class "Default")
      (node (ref "U1") (pin "17") (pinfunction "PC2/SPI2_MISO_17") (pintype "passive"))
    )
    (net (code "68") (name "unconnected-(U1A-PC3{slash}SPI2_MOSI-Pad18)") (class "Default")
      (node (ref "U1") (pin "18") (pinfunction "PC3/SPI2_MOSI_18") (pintype "passive"))
    )
    (net (code "69") (name "unconnected-(U1A-PC6{slash}USART6-TX{slash}TIM3_CH1-Pad63)") (class "Default")
      (node (ref "U1") (pin "63") (pinfunction "PC6/USART6-TX/TIM3_CH1_63") (pintype "passive"))
    )
    (net (code "70") (name "unconnected-(U1A-PC7{slash}USART6_RX{slash}TIM3_CH2-Pad64)") (class "Default")
      (node (ref "U1") (pin "64") (pinfunction "PC7/USART6_RX/TIM3_CH2_64") (pintype "passive"))
    )
    (net (code "71") (name "unconnected-(U1A-PC8{slash}TIM3_CH3-Pad65)") (class "Default")
      (node (ref "U1") (pin "65") (pinfunction "PC8/TIM3_CH3_65") (pintype "passive"))
    )
    (net (code "72") (name "unconnected-(U1A-PC9{slash}TIM3_CH4-Pad66)") (class "Default")
      (node (ref "U1") (pin "66") (pinfunction "PC9/TIM3_CH4_66") (pintype "passive"))
    )
    (net (code "73") (name "unconnected-(U1A-PC10{slash}SPI3_SCK{slash}USART3_TX{slash}UART4_TX-Pad78)") (class "Default")
      (node (ref "U1") (pin "78") (pinfunction "PC10/SPI3_SCK/USART3_TX/UART4_TX_78") (pintype "passive"))
    )
    (net (code "74") (name "unconnected-(U1A-PC11{slash}SPI3_MISO{slash}USART3_RX{slash}UART4_RX-Pad79)") (class "Default")
      (node (ref "U1") (pin "79") (pinfunction "PC11/SPI3_MISO/USART3_RX/UART4_RX_79") (pintype "passive"))
    )
    (net (code "75") (name "unconnected-(U1A-PC12{slash}SPI3_MOSI{slash}UART5_TX-Pad80)") (class "Default")
      (node (ref "U1") (pin "80") (pinfunction "PC12/SPI3_MOSI/UART5_TX_80") (pintype "passive+no_connect"))
    )
    (net (code "76") (name "unconnected-(U1A-PC13-RTC_TAMP1-Pad7)") (class "Default")
      (node (ref "U1") (pin "7") (pinfunction "PC13-RTC_TAMP1_7") (pintype "passive+no_connect"))
    )
    (net (code "77") (name "unconnected-(U1A-PC14-OSC32_IN-Pad8)") (class "Default")
      (node (ref "U1") (pin "8") (pinfunction "PC14-OSC32_IN_8") (pintype "passive+no_connect"))
    )
    (net (code "78") (name "unconnected-(U1A-PC15-OSC32_OUT-Pad9)") (class "Default")
      (node (ref "U1") (pin "9") (pinfunction "PC15-OSC32_OUT_9") (pintype "passive+no_connect"))
    )
    (net (code "79") (name "unconnected-(U1A-PD0{slash}UART4_RX-Pad81)") (class "Default")
      (node (ref "U1") (pin "81") (pinfunction "PD0/UART4_RX_81") (pintype "passive+no_connect"))
    )
    (net (code "80") (name "unconnected-(U1A-PD4-Pad85)") (class "Default")
      (node (ref "U1") (pin "85") (pinfunction "PD4_85") (pintype "passive"))
    )
    (net (code "81") (name "unconnected-(U1A-PD7{slash}SPI1_MOSI-Pad88)") (class "Default")
      (node (ref "U1") (pin "88") (pinfunction "PD7/SPI1_MOSI_88") (pintype "passive"))
    )
    (net (code "82") (name "unconnected-(U1A-PD8-Pad55)") (class "Default")
      (node (ref "U1") (pin "55") (pinfunction "PD8_55") (pintype "passive"))
    )
    (net (code "83") (name "unconnected-(U1A-PD9{slash}USART3_RX-Pad56)") (class "Default")
      (node (ref "U1") (pin "56") (pinfunction "PD9/USART3_RX_56") (pintype "passive"))
    )
    (net (code "84") (name "unconnected-(U1A-PD10-Pad57)") (class "Default")
      (node (ref "U1") (pin "57") (pinfunction "PD10_57") (pintype "passive"))
    )
    (net (code "85") (name "unconnected-(U1A-PD11-Pad58)") (class "Default")
      (node (ref "U1") (pin "58") (pinfunction "PD11_58") (pintype "passive"))
    )
    (net (code "86") (name "unconnected-(U1A-PD12{slash}TIM4_CH1-Pad59)") (class "Default")
      (node (ref "U1") (pin "59") (pinfunction "PD12/TIM4_CH1_59") (pintype "passive"))
    )
    (net (code "87") (name "unconnected-(U1A-PD13{slash}TIM4_CH2-Pad60)") (class "Default")
      (node (ref "U1") (pin "60") (pinfunction "PD13/TIM4_CH2_60") (pintype "passive"))
    )
    (net (code "88") (name "unconnected-(U1A-PD14{slash}TIM4_CH3-Pad61)") (class "Default")
      (node (ref "U1") (pin "61") (pinfunction "PD14/TIM4_CH3_61") (pintype "passive"))
    )
    (net (code "89") (name "unconnected-(U1A-PD15{slash}TIM4_CH4-Pad62)") (class "Default")
      (node (ref "U1") (pin "62") (pinfunction "PD15/TIM4_CH4_62") (pintype "passive"))
    )
    (net (code "90") (name "unconnected-(U1B-PE0{slash}UART8_RX-Pad97)") (class "Default")
      (node (ref "U1") (pin "97") (pinfunction "PE0/UART8_RX_97") (pintype "passive+no_connect"))
    )
    (net (code "91") (name "unconnected-(U1B-PE1{slash}UART8_TX-Pad98)") (class "Default")
      (node (ref "U1") (pin "98") (pinfunction "PE1/UART8_TX_98") (pintype "passive+no_connect"))
    )
    (net (code "92") (name "unconnected-(U1B-PE2{slash}SPI4_SCK-Pad1)") (class "Default")
      (node (ref "U1") (pin "1") (pinfunction "PE2/SPI4_SCK_1") (pintype "passive+no_connect"))
    )
    (net (code "93") (name "unconnected-(U1B-PE3-Pad2)") (class "Default")
      (node (ref "U1") (pin "2") (pinfunction "PE3_2") (pintype "passive+no_connect"))
    )
    (net (code "94") (name "unconnected-(U1B-PE4-Pad3)") (class "Default")
      (node (ref "U1") (pin "3") (pinfunction "PE4_3") (pintype "passive+no_connect"))
    )
    (net (code "95") (name "unconnected-(U1B-PE5{slash}SPI4_MISO-Pad4)") (class "Default")
      (node (ref "U1") (pin "4") (pinfunction "PE5/SPI4_MISO_4") (pintype "passive+no_connect"))
    )
    (net (code "96") (name "unconnected-(U1B-PE6{slash}SPI4_MOSI-Pad5)") (class "Default")
      (node (ref "U1") (pin "5") (pinfunction "PE6/SPI4_MOSI_5") (pintype "passive+no_connect"))
    )
    (net (code "97") (name "unconnected-(U1B-PE7{slash}UART7_RX-Pad37)") (class "Default")
      (node (ref "U1") (pin "37") (pinfunction "PE7/UART7_RX_37") (pintype "passive+no_connect"))
    )
    (net (code "98") (name "unconnected-(U1B-PE8{slash}UART7_TX-Pad38)") (class "Default")
      (node (ref "U1") (pin "38") (pinfunction "PE8/UART7_TX_38") (pintype "passive+no_connect"))
    )
    (net (code "99") (name "unconnected-(U1B-PE9{slash}TIM1_CH1-Pad39)") (class "Default")
      (node (ref "U1") (pin "39") (pinfunction "PE9/TIM1_CH1_39") (pintype "passive+no_connect"))
    )
    (net (code "100") (name "unconnected-(U1B-PE10-Pad40)") (class "Default")
      (node (ref "U1") (pin "40") (pinfunction "PE10_40") (pintype "passive+no_connect"))
    )
    (net (code "101") (name "unconnected-(U1B-PE11{slash}SPI4_NSS{slash}TIM1_CH2-Pad41)") (class "Default")
      (node (ref "U1") (pin "41") (pinfunction "PE11/SPI4_NSS/TIM1_CH2_41") (pintype "passive+no_connect"))
    )
    (net (code "102") (name "unconnected-(U1B-PE12{slash}SPI4_SCK-Pad42)") (class "Default")
      (node (ref "U1") (pin "42") (pinfunction "PE12/SPI4_SCK_42") (pintype "passive+no_connect"))
    )
    (net (code "103") (name "unconnected-(U1B-PE13{slash}SPI4_MISO{slash}TIM1_CH3-Pad43)") (class "Default")
      (node (ref "U1") (pin "43") (pinfunction "PE13/SPI4_MISO/TIM1_CH3_43") (pintype "passive+no_connect"))
    )
    (net (code "104") (name "unconnected-(U1B-PE14{slash}SPI4_MOSI{slash}TIM1_CH4-Pad44)") (class "Default")
      (node (ref "U1") (pin "44") (pinfunction "PE14/SPI4_MOSI/TIM1_CH4_44") (pintype "passive+no_connect"))
    )
    (net (code "105") (name "unconnected-(U1B-PE15-Pad45)") (class "Default")
      (node (ref "U1") (pin "45") (pinfunction "PE15_45") (pintype "passive+no_connect"))
    )
    (net (code "106") (name "unconnected-(U1B-PH1-OSC_OUT-Pad13)") (class "Default")
      (node (ref "U1") (pin "13") (pinfunction "PH1-OSC_OUT_13") (pintype "passive+no_connect"))
    )
    (net (code "107") (name "unconnected-(U3-CTS#-Pad28)") (class "Default")
      (node (ref "U3") (pin "28") (pinfunction "CTS#_28") (pintype "input+no_connect"))
    )
    (net (code "108") (name "unconnected-(U3-DCD#-Pad26)") (class "Default")
      (node (ref "U3") (pin "26") (pinfunction "DCD#_26") (pintype "input+no_connect"))
    )
    (net (code "109") (name "unconnected-(U3-DSR#-Pad7)") (class "Default")
      (node (ref "U3") (pin "7") (pinfunction "DSR#_7") (pintype "input+no_connect"))
    )
    (net (code "110") (name "unconnected-(U3-DTR#-Pad11)") (class "Default")
      (node (ref "U3") (pin "11") (pinfunction "DTR#_11") (pintype "output+no_connect"))
    )
    (net (code "111") (name "unconnected-(U3-FCE-Pad10)") (class "Default")
      (node (ref "U3") (pin "10") (pinfunction "FCE_10") (pintype "input+no_connect"))
    )
    (net (code "112") (name "unconnected-(U3-RI#-Pad27)") (class "Default")
      (node (ref "U3") (pin "27") (pinfunction "RI#_27") (pintype "input+no_connect"))
    )
    (net (code "113") (name "unconnected-(U3-RTS#-Pad25)") (class "Default")
      (node (ref "U3") (pin "25") (pinfunction "RTS#_25") (pintype "output+no_connect"))
    )
    (net (code "114") (name "unconnected-(U3-TNOW-Pad17)") (class "Default")
      (node (ref "U3") (pin "17") (pinfunction "TNOW_17") (pintype "output+no_connect"))
    )
    (net (code "115") (name "unconnected-(U8-PD-Pad5)") (class "Default")
      (node (ref "U8") (pin "5") (pinfunction "PD_5") (pintype "passive"))
    )
  )
)
